# 1-Schematic_GPIO_WAVER_15PIN.net
KiCad netlist of a schematic drawn in EasyEDA
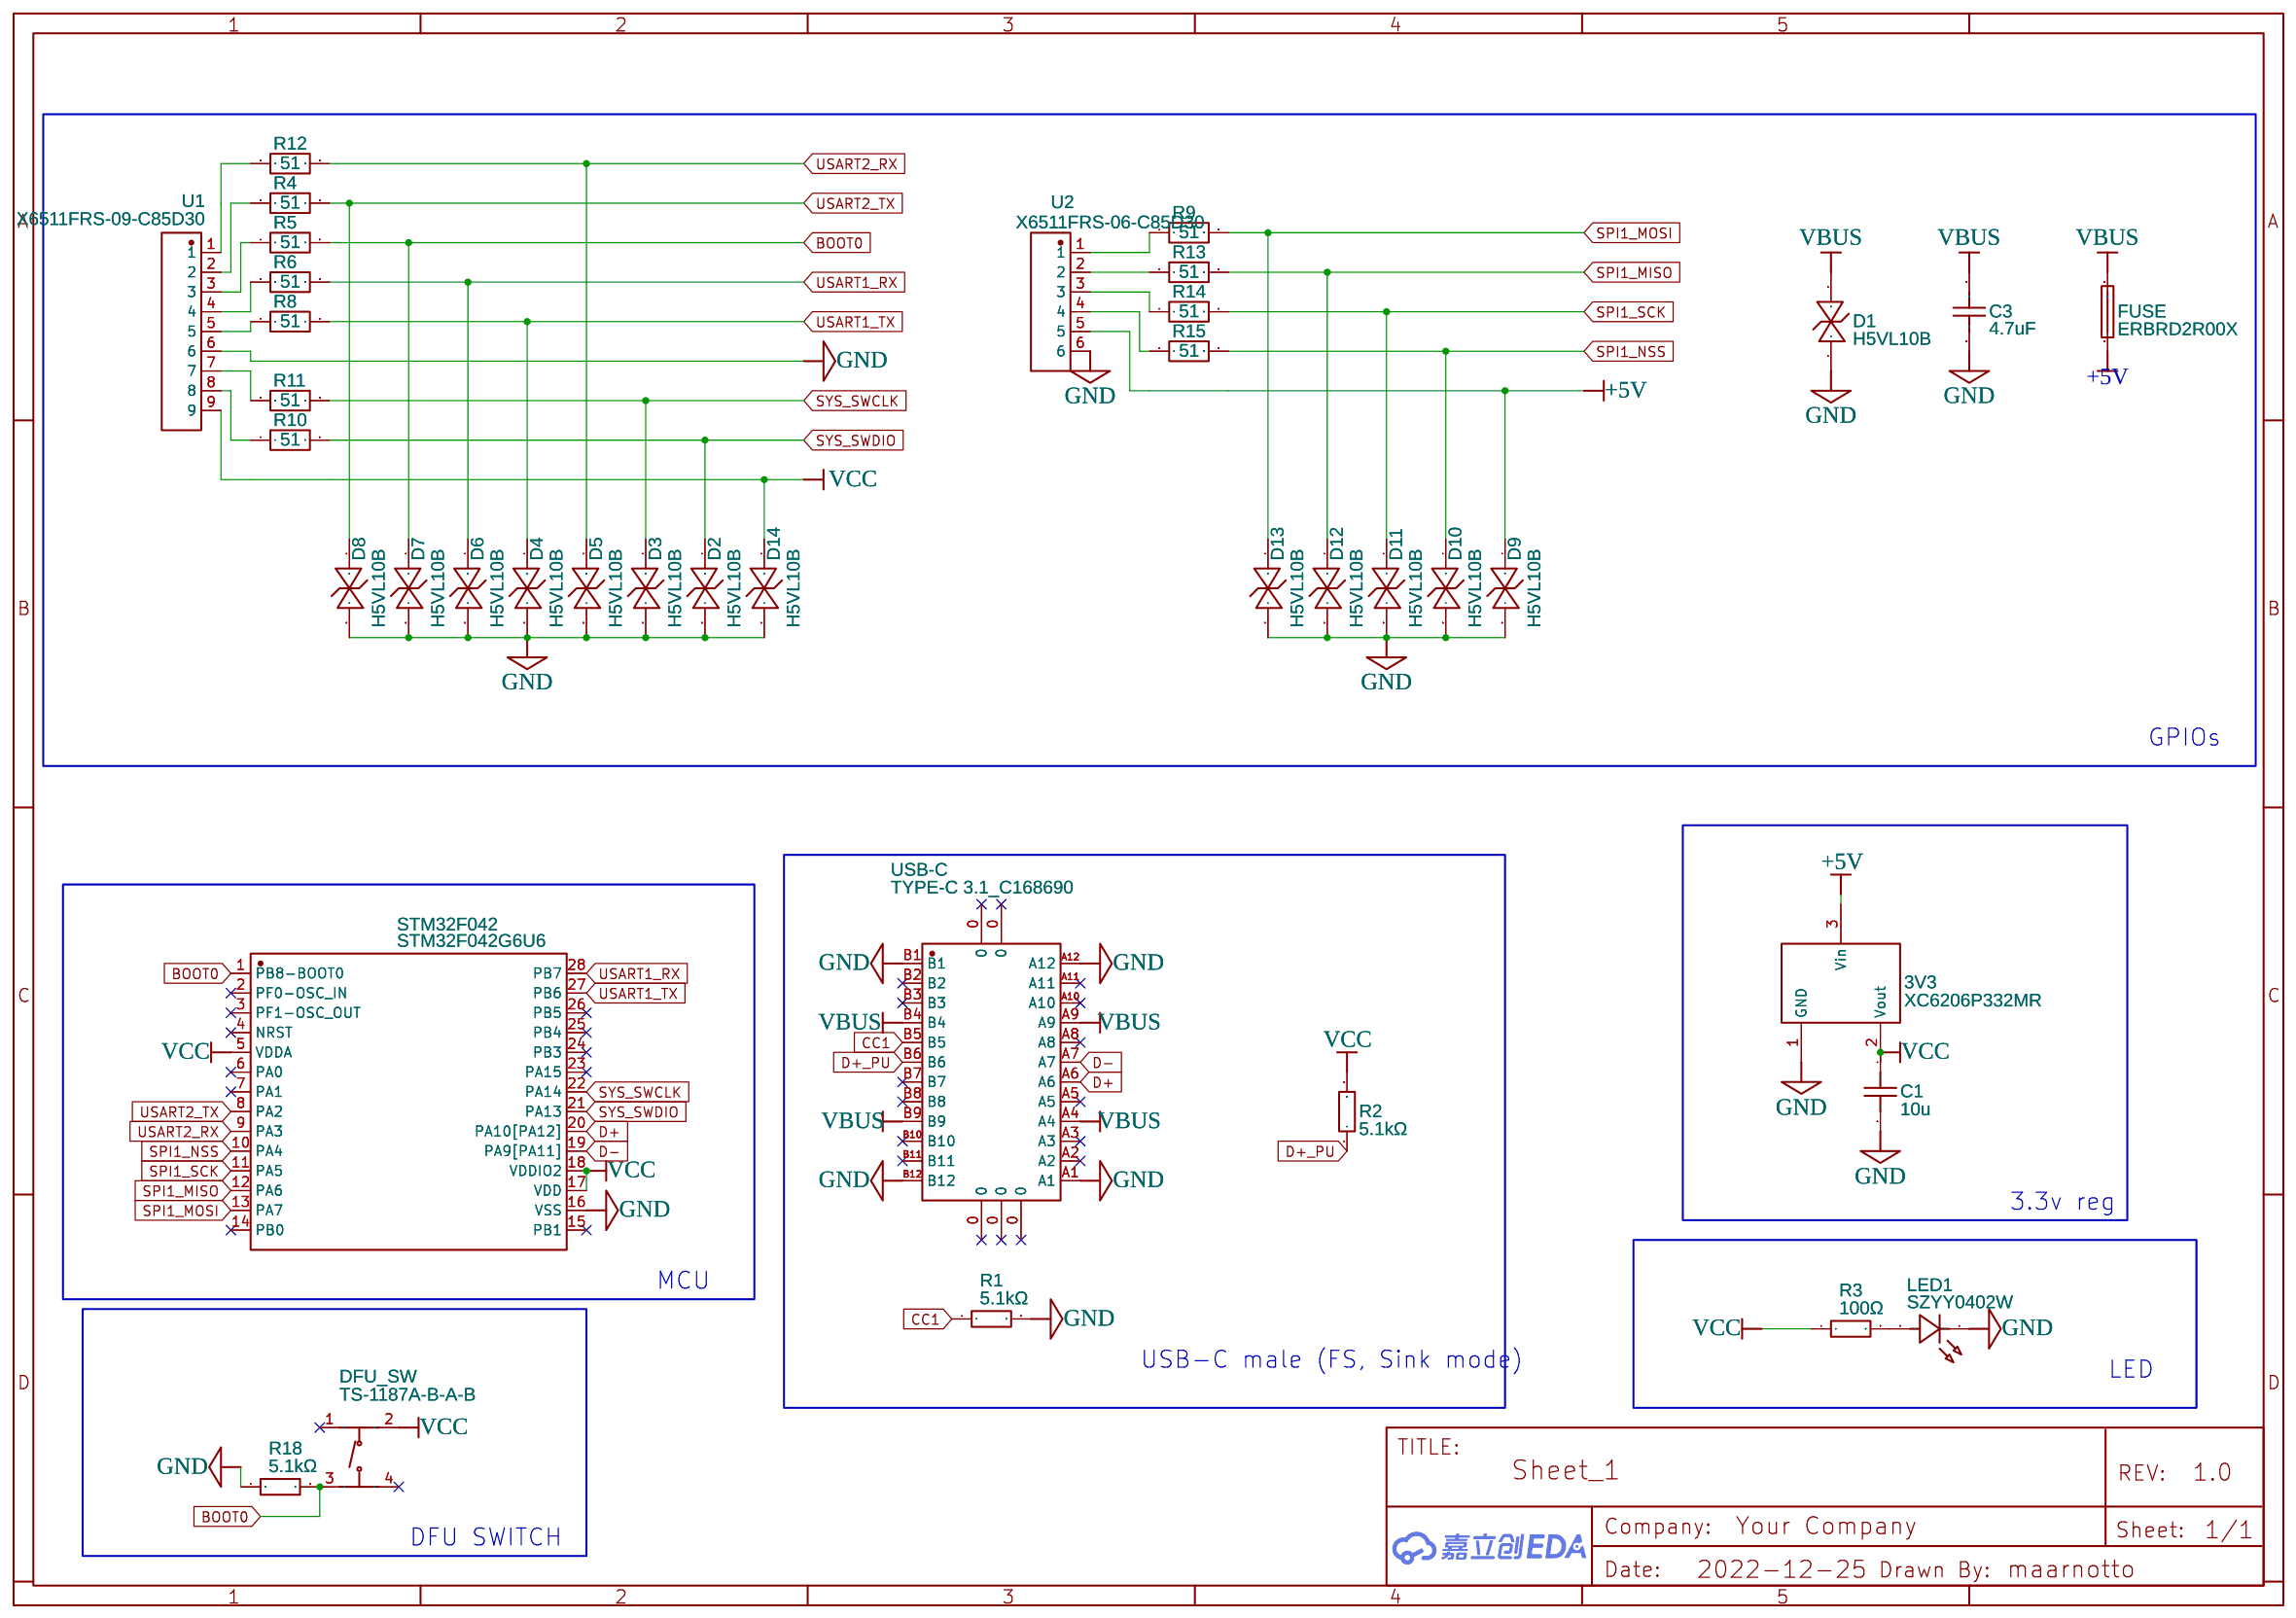
[diagram p0: schematic sheet]

(export (version "E")
  (design (tool "Eeschema 10.0.6"))
  (components
    (comp (ref "3V3")
      (value "XC6206P332MR")
      (fields (field (name "Manufacturer") "TOREX(特瑞仕)"))
      (libsource (lib "") (part "XC6206P332MR"))
    )
    (comp (ref "C1") (value "10u") (libsource (lib "") (part "C_0603_US")))
    (comp (ref "C3") (value "4.7uF") (libsource (lib "") (part "C_0603_US_1")))
    (comp (ref "D1")
      (value "H5VL10B")
      (fields (field (name "Manufacturer") "宏迦橙"))
      (libsource (lib "") (part "H5VL10B"))
    )
    (comp (ref "D2")
      (value "H5VL10B")
      (fields (field (name "Manufacturer") "宏迦橙"))
      (libsource (lib "") (part "H5VL10B"))
    )
    (comp (ref "D3")
      (value "H5VL10B")
      (fields (field (name "Manufacturer") "宏迦橙"))
      (libsource (lib "") (part "H5VL10B"))
    )
    (comp (ref "D4")
      (value "H5VL10B")
      (fields (field (name "Manufacturer") "宏迦橙"))
      (libsource (lib "") (part "H5VL10B"))
    )
    (comp (ref "D5")
      (value "H5VL10B")
      (fields (field (name "Manufacturer") "宏迦橙"))
      (libsource (lib "") (part "H5VL10B"))
    )
    (comp (ref "D6")
      (value "H5VL10B")
      (fields (field (name "Manufacturer") "宏迦橙"))
      (libsource (lib "") (part "H5VL10B"))
    )
    (comp (ref "D7")
      (value "H5VL10B")
      (fields (field (name "Manufacturer") "宏迦橙"))
      (libsource (lib "") (part "H5VL10B"))
    )
    (comp (ref "D8")
      (value "H5VL10B")
      (fields (field (name "Manufacturer") "宏迦橙"))
      (libsource (lib "") (part "H5VL10B"))
    )
    (comp (ref "D9")
      (value "H5VL10B")
      (fields (field (name "Manufacturer") "宏迦橙"))
      (libsource (lib "") (part "H5VL10B"))
    )
    (comp (ref "D10")
      (value "H5VL10B")
      (fields (field (name "Manufacturer") "宏迦橙"))
      (libsource (lib "") (part "H5VL10B"))
    )
    (comp (ref "D11")
      (value "H5VL10B")
      (fields (field (name "Manufacturer") "宏迦橙"))
      (libsource (lib "") (part "H5VL10B"))
    )
    (comp (ref "D12")
      (value "H5VL10B")
      (fields (field (name "Manufacturer") "宏迦橙"))
      (libsource (lib "") (part "H5VL10B"))
    )
    (comp (ref "D13")
      (value "H5VL10B")
      (fields (field (name "Manufacturer") "宏迦橙"))
      (libsource (lib "") (part "H5VL10B"))
    )
    (comp (ref "D14")
      (value "H5VL10B")
      (fields (field (name "Manufacturer") "宏迦橙"))
      (libsource (lib "") (part "H5VL10B"))
    )
    (comp (ref "DFU_SW")
      (value "TS-1187A-B-A-B")
      (fields (field (name "Manufacturer") "XKB Connectivity(中国星坤)"))
      (libsource (lib "") (part "TS-1187A-B-A-B"))
    )
    (comp (ref "FUSE")
      (value "ERBRD2R00X")
      (fields (field (name "Manufacturer") "PANASONIC(松下)"))
      (libsource (lib "") (part "ERBRD2R00X"))
    )
    (comp (ref "LED1")
      (value "SZYY0402W")
      (fields (field (name "Manufacturer") "yongyu(永裕光电)"))
      (libsource (lib "") (part "SZYY0402W"))
    )
    (comp (ref "R1")
      (value "5.1kΩ")
      (fields
        (field (name "Manufacturer Part") "0402WGF5101TCE")
        (field (name "Manufacturer") "UNI-ROYAL(厚声)")
      )
      (libsource (lib "") (part "0402WGF5101TCE"))
    )
    (comp (ref "R2")
      (value "5.1kΩ")
      (fields
        (field (name "Manufacturer Part") "0402WGF5101TCE")
        (field (name "Manufacturer") "UNI-ROYAL(厚声)")
      )
      (libsource (lib "") (part "0402WGF5101TCE_1"))
    )
    (comp (ref "R3")
      (value "100Ω")
      (fields
        (field (name "Manufacturer Part") "0402WGF1000TCE")
        (field (name "Manufacturer") "UNI-ROYAL(厚声)")
      )
      (libsource (lib "") (part "0402WGF1000TCE"))
    )
    (comp (ref "R4") (value "51") (libsource (lib "") (part "R_0603_EU")))
    (comp (ref "R5") (value "51") (libsource (lib "") (part "R_0603_EU")))
    (comp (ref "R6") (value "51") (libsource (lib "") (part "R_0603_EU")))
    (comp (ref "R8") (value "51") (libsource (lib "") (part "R_0603_EU")))
    (comp (ref "R9") (value "51") (libsource (lib "") (part "R_0603_EU")))
    (comp (ref "R10") (value "51") (libsource (lib "") (part "R_0603_EU")))
    (comp (ref "R11") (value "51") (libsource (lib "") (part "R_0603_EU")))
    (comp (ref "R12") (value "51") (libsource (lib "") (part "R_0603_EU")))
    (comp (ref "R13") (value "51") (libsource (lib "") (part "R_0603_EU")))
    (comp (ref "R14") (value "51") (libsource (lib "") (part "R_0603_EU")))
    (comp (ref "R15") (value "51") (libsource (lib "") (part "R_0603_EU")))
    (comp (ref "R18")
      (value "5.1kΩ")
      (fields
        (field (name "Manufacturer Part") "0402WGF5101TCE")
        (field (name "Manufacturer") "UNI-ROYAL(厚声)")
      )
      (libsource (lib "") (part "0402WGF5101TCE"))
    )
    (comp (ref "STM32F042")
      (value "STM32F042G6U6")
      (fields (field (name "Manufacturer") "ST(意法半导体)"))
      (libsource (lib "") (part "STM32F042G6U6"))
    )
    (comp (ref "U1")
      (value "X6511FRS-09-C85D30")
      (fields (field (name "Manufacturer") "XKB Connectivity(中国星坤)"))
      (libsource (lib "") (part "X6511FRS-09-C85D30"))
    )
    (comp (ref "U2")
      (value "X6511FRS-06-C85D30")
      (fields (field (name "Manufacturer") "XKB Connectivity(中国星坤)"))
      (libsource (lib "") (part "X6511FRS-06-C85D30"))
    )
    (comp (ref "USB-C")
      (value "TYPE-C 3.1_C168690")
      (fields (field (name "Manufacturer Part") "918-118A2021Y40000") (field (name "Manufacturer") "精拓金"))
      (libsource (lib "") (part "TYPE-C 3.1_C168690"))
    )
  )
  (nets
    (net (code "1") (name "+5V") (class "Default")
      (node (ref "3V3") (pin "3") (pinfunction "Vin_3") (pintype "unspecified"))
      (node (ref "D9") (pin "1") (pinfunction "C_1") (pintype "unspecified"))
      (node (ref "FUSE") (pin "1") (pinfunction "1_1") (pintype "unspecified"))
      (node (ref "U2") (pin "5") (pinfunction "5_5") (pintype "unspecified"))
    )
    (net (code "2") (name "BOOT0") (class "Default")
      (node (ref "D7") (pin "1") (pinfunction "C_1") (pintype "unspecified"))
      (node (ref "DFU_SW") (pin "3") (pinfunction "C_3") (pintype "unspecified"))
      (node (ref "R18") (pin "2") (pinfunction "2_2") (pintype "input"))
      (node (ref "R5") (pin "2") (pinfunction "2_2") (pintype "unspecified"))
      (node (ref "STM32F042") (pin "1") (pinfunction "PB8-BOOT0_1") (pintype "unspecified"))
    )
    (net (code "3") (name "CC1") (class "Default")
      (node (ref "R1") (pin "1") (pinfunction "1_1") (pintype "input"))
      (node (ref "USB-C") (pin "B5") (pinfunction "B5_B5") (pintype "unspecified"))
    )
    (net (code "4") (name "D+") (class "Default")
      (node (ref "STM32F042") (pin "20") (pinfunction "PA10[PA12]_20") (pintype "unspecified"))
      (node (ref "USB-C") (pin "A6") (pinfunction "A6_A6") (pintype "unspecified"))
    )
    (net (code "5") (name "D+_PU") (class "Default")
      (node (ref "R2") (pin "1") (pinfunction "1_1") (pintype "input"))
      (node (ref "USB-C") (pin "B6") (pinfunction "B6_B6") (pintype "unspecified"))
    )
    (net (code "6") (name "D-") (class "Default")
      (node (ref "STM32F042") (pin "19") (pinfunction "PA9[PA11]_19") (pintype "unspecified"))
      (node (ref "USB-C") (pin "A7") (pinfunction "A7_A7") (pintype "unspecified"))
    )
    (net (code "7") (name "GND") (class "Default")
      (node (ref "3V3") (pin "1") (pinfunction "GND_1") (pintype "unspecified"))
      (node (ref "C1") (pin "2") (pinfunction "2_2") (pintype "unspecified"))
      (node (ref "C3") (pin "1") (pinfunction "1_1") (pintype "unspecified"))
      (node (ref "D1") (pin "2") (pinfunction "A_2") (pintype "unspecified"))
      (node (ref "D10") (pin "2") (pinfunction "A_2") (pintype "unspecified"))
      (node (ref "D11") (pin "2") (pinfunction "A_2") (pintype "unspecified"))
      (node (ref "D12") (pin "2") (pinfunction "A_2") (pintype "unspecified"))
      (node (ref "D13") (pin "2") (pinfunction "A_2") (pintype "unspecified"))
      (node (ref "D14") (pin "2") (pinfunction "A_2") (pintype "unspecified"))
      (node (ref "D2") (pin "2") (pinfunction "A_2") (pintype "unspecified"))
      (node (ref "D3") (pin "2") (pinfunction "A_2") (pintype "unspecified"))
      (node (ref "D4") (pin "2") (pinfunction "A_2") (pintype "unspecified"))
      (node (ref "D5") (pin "2") (pinfunction "A_2") (pintype "unspecified"))
      (node (ref "D6") (pin "2") (pinfunction "A_2") (pintype "unspecified"))
      (node (ref "D7") (pin "2") (pinfunction "A_2") (pintype "unspecified"))
      (node (ref "D8") (pin "2") (pinfunction "A_2") (pintype "unspecified"))
      (node (ref "D9") (pin "2") (pinfunction "A_2") (pintype "unspecified"))
      (node (ref "LED1") (pin "1") (pinfunction "K_1") (pintype "unspecified"))
      (node (ref "R1") (pin "2") (pinfunction "2_2") (pintype "input"))
      (node (ref "R18") (pin "1") (pinfunction "1_1") (pintype "input"))
      (node (ref "STM32F042") (pin "16") (pinfunction "VSS_16") (pintype "unspecified"))
      (node (ref "U1") (pin "6") (pinfunction "6_6") (pintype "unspecified"))
      (node (ref "U2") (pin "6") (pinfunction "6_6") (pintype "unspecified"))
      (node (ref "USB-C") (pin "A1") (pinfunction "A1_A1") (pintype "unspecified"))
      (node (ref "USB-C") (pin "A12") (pinfunction "A12_A12") (pintype "unspecified"))
      (node (ref "USB-C") (pin "B1") (pinfunction "B1_B1") (pintype "unspecified"))
      (node (ref "USB-C") (pin "B12") (pinfunction "B12_B12") (pintype "unspecified"))
    )
    (net (code "8") (name "Net-(LED1-A)") (class "Default")
      (node (ref "LED1") (pin "2") (pinfunction "A_2") (pintype "unspecified"))
      (node (ref "R3") (pin "2") (pinfunction "2_2") (pintype "input"))
    )
    (net (code "9") (name "Net-(R4-Pad1)") (class "Default")
      (node (ref "R4") (pin "1") (pinfunction "1_1") (pintype "unspecified"))
      (node (ref "U1") (pin "2") (pinfunction "2_2") (pintype "unspecified"))
    )
    (net (code "10") (name "Net-(R5-Pad1)") (class "Default")
      (node (ref "R5") (pin "1") (pinfunction "1_1") (pintype "unspecified"))
      (node (ref "U1") (pin "3") (pinfunction "3_3") (pintype "unspecified"))
    )
    (net (code "11") (name "Net-(R6-Pad1)") (class "Default")
      (node (ref "R6") (pin "1") (pinfunction "1_1") (pintype "unspecified"))
      (node (ref "U1") (pin "4") (pinfunction "4_4") (pintype "unspecified"))
    )
    (net (code "12") (name "Net-(R8-Pad1)") (class "Default")
      (node (ref "R8") (pin "1") (pinfunction "1_1") (pintype "unspecified"))
      (node (ref "U1") (pin "5") (pinfunction "5_5") (pintype "unspecified"))
    )
    (net (code "13") (name "Net-(R9-Pad1)") (class "Default")
      (node (ref "R9") (pin "1") (pinfunction "1_1") (pintype "unspecified"))
      (node (ref "U2") (pin "1") (pinfunction "1_1") (pintype "unspecified"))
    )
    (net (code "14") (name "Net-(R10-Pad1)") (class "Default")
      (node (ref "R10") (pin "1") (pinfunction "1_1") (pintype "unspecified"))
      (node (ref "U1") (pin "8") (pinfunction "8_8") (pintype "unspecified"))
    )
    (net (code "15") (name "Net-(R11-Pad1)") (class "Default")
      (node (ref "R11") (pin "1") (pinfunction "1_1") (pintype "unspecified"))
      (node (ref "U1") (pin "7") (pinfunction "7_7") (pintype "unspecified"))
    )
    (net (code "16") (name "Net-(R12-Pad1)") (class "Default")
      (node (ref "R12") (pin "1") (pinfunction "1_1") (pintype "unspecified"))
      (node (ref "U1") (pin "1") (pinfunction "1_1") (pintype "unspecified"))
    )
    (net (code "17") (name "Net-(R13-Pad1)") (class "Default")
      (node (ref "R13") (pin "1") (pinfunction "1_1") (pintype "unspecified"))
      (node (ref "U2") (pin "2") (pinfunction "2_2") (pintype "unspecified"))
    )
    (net (code "18") (name "Net-(R14-Pad1)") (class "Default")
      (node (ref "R14") (pin "1") (pinfunction "1_1") (pintype "unspecified"))
      (node (ref "U2") (pin "3") (pinfunction "3_3") (pintype "unspecified"))
    )
    (net (code "19") (name "Net-(R15-Pad1)") (class "Default")
      (node (ref "R15") (pin "1") (pinfunction "1_1") (pintype "unspecified"))
      (node (ref "U2") (pin "4") (pinfunction "4_4") (pintype "unspecified"))
    )
    (net (code "20") (name "SPI1_MISO") (class "Default")
      (node (ref "D12") (pin "1") (pinfunction "C_1") (pintype "unspecified"))
      (node (ref "R13") (pin "2") (pinfunction "2_2") (pintype "unspecified"))
      (node (ref "STM32F042") (pin "12") (pinfunction "PA6_12") (pintype "unspecified"))
    )
    (net (code "21") (name "SPI1_MOSI") (class "Default")
      (node (ref "D13") (pin "1") (pinfunction "C_1") (pintype "unspecified"))
      (node (ref "R9") (pin "2") (pinfunction "2_2") (pintype "unspecified"))
      (node (ref "STM32F042") (pin "13") (pinfunction "PA7_13") (pintype "unspecified"))
    )
    (net (code "22") (name "SPI1_NSS") (class "Default")
      (node (ref "D10") (pin "1") (pinfunction "C_1") (pintype "unspecified"))
      (node (ref "R15") (pin "2") (pinfunction "2_2") (pintype "unspecified"))
      (node (ref "STM32F042") (pin "10") (pinfunction "PA4_10") (pintype "unspecified"))
    )
    (net (code "23") (name "SPI1_SCK") (class "Default")
      (node (ref "D11") (pin "1") (pinfunction "C_1") (pintype "unspecified"))
      (node (ref "R14") (pin "2") (pinfunction "2_2") (pintype "unspecified"))
      (node (ref "STM32F042") (pin "11") (pinfunction "PA5_11") (pintype "unspecified"))
    )
    (net (code "24") (name "SYS_SWCLK") (class "Default")
      (node (ref "D3") (pin "1") (pinfunction "C_1") (pintype "unspecified"))
      (node (ref "R11") (pin "2") (pinfunction "2_2") (pintype "unspecified"))
      (node (ref "STM32F042") (pin "22") (pinfunction "PA14_22") (pintype "unspecified"))
    )
    (net (code "25") (name "SYS_SWDIO") (class "Default")
      (node (ref "D2") (pin "1") (pinfunction "C_1") (pintype "unspecified"))
      (node (ref "R10") (pin "2") (pinfunction "2_2") (pintype "unspecified"))
      (node (ref "STM32F042") (pin "21") (pinfunction "PA13_21") (pintype "unspecified"))
    )
    (net (code "26") (name "USART1_RX") (class "Default")
      (node (ref "D6") (pin "1") (pinfunction "C_1") (pintype "unspecified"))
      (node (ref "R6") (pin "2") (pinfunction "2_2") (pintype "unspecified"))
      (node (ref "STM32F042") (pin "28") (pinfunction "PB7_28") (pintype "unspecified"))
    )
    (net (code "27") (name "USART1_TX") (class "Default")
      (node (ref "D4") (pin "1") (pinfunction "C_1") (pintype "unspecified"))
      (node (ref "R8") (pin "2") (pinfunction "2_2") (pintype "unspecified"))
      (node (ref "STM32F042") (pin "27") (pinfunction "PB6_27") (pintype "unspecified"))
    )
    (net (code "28") (name "USART2_RX") (class "Default")
      (node (ref "D5") (pin "1") (pinfunction "C_1") (pintype "unspecified"))
      (node (ref "R12") (pin "2") (pinfunction "2_2") (pintype "unspecified"))
      (node (ref "STM32F042") (pin "9") (pinfunction "PA3_9") (pintype "unspecified"))
    )
    (net (code "29") (name "USART2_TX") (class "Default")
      (node (ref "D8") (pin "1") (pinfunction "C_1") (pintype "unspecified"))
      (node (ref "R4") (pin "2") (pinfunction "2_2") (pintype "unspecified"))
      (node (ref "STM32F042") (pin "8") (pinfunction "PA2_8") (pintype "unspecified"))
    )
    (net (code "30") (name "VBUS") (class "Default")
      (node (ref "C3") (pin "2") (pinfunction "2_2") (pintype "unspecified"))
      (node (ref "D1") (pin "1") (pinfunction "C_1") (pintype "unspecified"))
      (node (ref "FUSE") (pin "2") (pinfunction "2_2") (pintype "unspecified"))
      (node (ref "USB-C") (pin "A4") (pinfunction "A4_A4") (pintype "unspecified"))
      (node (ref "USB-C") (pin "A9") (pinfunction "A9_A9") (pintype "unspecified"))
      (node (ref "USB-C") (pin "B4") (pinfunction "B4_B4") (pintype "unspecified"))
      (node (ref "USB-C") (pin "B9") (pinfunction "B9_B9") (pintype "unspecified"))
    )
    (net (code "31") (name "VCC") (class "Default")
      (node (ref "3V3") (pin "2") (pinfunction "Vout_2") (pintype "unspecified"))
      (node (ref "C1") (pin "1") (pinfunction "1_1") (pintype "unspecified"))
      (node (ref "D14") (pin "1") (pinfunction "C_1") (pintype "unspecified"))
      (node (ref "DFU_SW") (pin "2") (pinfunction "B_2") (pintype "unspecified"))
      (node (ref "R2") (pin "2") (pinfunction "2_2") (pintype "input"))
      (node (ref "R3") (pin "1") (pinfunction "1_1") (pintype "input"))
      (node (ref "STM32F042") (pin "17") (pinfunction "VDD_17") (pintype "unspecified"))
      (node (ref "STM32F042") (pin "18") (pinfunction "VDDIO2_18") (pintype "unspecified"))
      (node (ref "STM32F042") (pin "5") (pinfunction "VDDA_5") (pintype "unspecified"))
      (node (ref "U1") (pin "9") (pinfunction "9_9") (pintype "unspecified"))
    )
    (net (code "32") (name "unconnected-(DFU_SW-A-Pad1)") (class "Default")
      (node (ref "DFU_SW") (pin "1") (pinfunction "A_1") (pintype "unspecified+no_connect"))
    )
    (net (code "33") (name "unconnected-(DFU_SW-D-Pad4)") (class "Default")
      (node (ref "DFU_SW") (pin "4") (pinfunction "D_4") (pintype "unspecified+no_connect"))
    )
    (net (code "34") (name "unconnected-(STM32F042-NRST-Pad4)") (class "Default")
      (node (ref "STM32F042") (pin "4") (pinfunction "NRST_4") (pintype "unspecified+no_connect"))
    )
    (net (code "35") (name "unconnected-(STM32F042-PA0-Pad6)") (class "Default")
      (node (ref "STM32F042") (pin "6") (pinfunction "PA0_6") (pintype "unspecified+no_connect"))
    )
    (net (code "36") (name "unconnected-(STM32F042-PA1-Pad7)") (class "Default")
      (node (ref "STM32F042") (pin "7") (pinfunction "PA1_7") (pintype "unspecified+no_connect"))
    )
    (net (code "37") (name "unconnected-(STM32F042-PA15-Pad23)") (class "Default")
      (node (ref "STM32F042") (pin "23") (pinfunction "PA15_23") (pintype "unspecified+no_connect"))
    )
    (net (code "38") (name "unconnected-(STM32F042-PB0-Pad14)") (class "Default")
      (node (ref "STM32F042") (pin "14") (pinfunction "PB0_14") (pintype "unspecified+no_connect"))
    )
    (net (code "39") (name "unconnected-(STM32F042-PB1-Pad15)") (class "Default")
      (node (ref "STM32F042") (pin "15") (pinfunction "PB1_15") (pintype "unspecified+no_connect"))
    )
    (net (code "40") (name "unconnected-(STM32F042-PB3-Pad24)") (class "Default")
      (node (ref "STM32F042") (pin "24") (pinfunction "PB3_24") (pintype "unspecified+no_connect"))
    )
    (net (code "41") (name "unconnected-(STM32F042-PB4-Pad25)") (class "Default")
      (node (ref "STM32F042") (pin "25") (pinfunction "PB4_25") (pintype "unspecified+no_connect"))
    )
    (net (code "42") (name "unconnected-(STM32F042-PB5-Pad26)") (class "Default")
      (node (ref "STM32F042") (pin "26") (pinfunction "PB5_26") (pintype "unspecified+no_connect"))
    )
    (net (code "43") (name "unconnected-(STM32F042-PF0-OSC_IN-Pad2)") (class "Default")
      (node (ref "STM32F042") (pin "2") (pinfunction "PF0-OSC_IN_2") (pintype "unspecified+no_connect"))
    )
    (net (code "44") (name "unconnected-(STM32F042-PF1-OSC_OUT-Pad3)") (class "Default")
      (node (ref "STM32F042") (pin "3") (pinfunction "PF1-OSC_OUT_3") (pintype "unspecified+no_connect"))
    )
    (net (code "45") (name "unconnected-(USB-C-Pad0)") (class "Default")
      (node (ref "USB-C") (pin "0") (pinfunction "0_0") (pintype "unspecified+no_connect"))
    )
    (net (code "46") (name "unconnected-(USB-C-Pad0)_1") (class "Default")
      (node (ref "USB-C") (pin "0") (pinfunction "0_0") (pintype "unspecified+no_connect"))
    )
    (net (code "47") (name "unconnected-(USB-C-Pad0)_2") (class "Default")
      (node (ref "USB-C") (pin "0") (pinfunction "0_0") (pintype "unspecified+no_connect"))
    )
    (net (code "48") (name "unconnected-(USB-C-Pad0)_3") (class "Default")
      (node (ref "USB-C") (pin "0") (pinfunction "0_0") (pintype "unspecified+no_connect"))
    )
    (net (code "49") (name "unconnected-(USB-C-Pad0)_4") (class "Default")
      (node (ref "USB-C") (pin "0") (pinfunction "0_0") (pintype "unspecified+no_connect"))
    )
    (net (code "50") (name "unconnected-(USB-C-PadA2)") (class "Default")
      (node (ref "USB-C") (pin "A2") (pinfunction "A2_A2") (pintype "unspecified+no_connect"))
    )
    (net (code "51") (name "unconnected-(USB-C-PadA3)") (class "Default")
      (node (ref "USB-C") (pin "A3") (pinfunction "A3_A3") (pintype "unspecified+no_connect"))
    )
    (net (code "52") (name "unconnected-(USB-C-PadA5)") (class "Default")
      (node (ref "USB-C") (pin "A5") (pinfunction "A5_A5") (pintype "unspecified+no_connect"))
    )
    (net (code "53") (name "unconnected-(USB-C-PadA8)") (class "Default")
      (node (ref "USB-C") (pin "A8") (pinfunction "A8_A8") (pintype "unspecified+no_connect"))
    )
    (net (code "54") (name "unconnected-(USB-C-PadA10)") (class "Default")
      (node (ref "USB-C") (pin "A10") (pinfunction "A10_A10") (pintype "unspecified+no_connect"))
    )
    (net (code "55") (name "unconnected-(USB-C-PadA11)") (class "Default")
      (node (ref "USB-C") (pin "A11") (pinfunction "A11_A11") (pintype "unspecified+no_connect"))
    )
    (net (code "56") (name "unconnected-(USB-C-PadB2)") (class "Default")
      (node (ref "USB-C") (pin "B2") (pinfunction "B2_B2") (pintype "unspecified+no_connect"))
    )
    (net (code "57") (name "unconnected-(USB-C-PadB3)") (class "Default")
      (node (ref "USB-C") (pin "B3") (pinfunction "B3_B3") (pintype "unspecified+no_connect"))
    )
    (net (code "58") (name "unconnected-(USB-C-PadB7)") (class "Default")
      (node (ref "USB-C") (pin "B7") (pinfunction "B7_B7") (pintype "unspecified+no_connect"))
    )
    (net (code "59") (name "unconnected-(USB-C-PadB8)") (class "Default")
      (node (ref "USB-C") (pin "B8") (pinfunction "B8_B8") (pintype "unspecified+no_connect"))
    )
    (net (code "60") (name "unconnected-(USB-C-PadB10)") (class "Default")
      (node (ref "USB-C") (pin "B10") (pinfunction "B10_B10") (pintype "unspecified+no_connect"))
    )
    (net (code "61") (name "unconnected-(USB-C-PadB11)") (class "Default")
      (node (ref "USB-C") (pin "B11") (pinfunction "B11_B11") (pintype "unspecified+no_connect"))
    )
  )
)
